# ISP-Adaptor.net
KiCad netlist of a schematic drawn in EAGLE
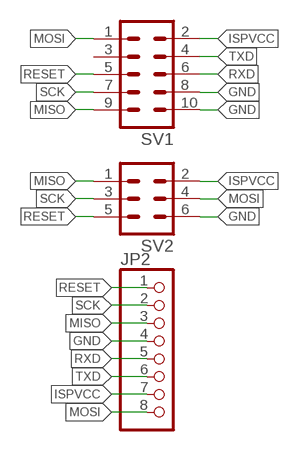
[diagram p0: schematic, sheet 1]

(export (version "E")
  (design (tool "Eeschema 10.0.6"))
  (components
    (comp (ref "JP2")
      (value "PINHD-1X8")
      (footprint "eagle-import:1X08")
      (libsource (lib "eagle-import") (part "PINHD-1X8"))
    )
    (comp (ref "SV1")
      (value "ML10")
      (footprint "eagle-import:ML10")
      (libsource (lib "eagle-import") (part "ML10"))
    )
    (comp (ref "SV2")
      (value "ML6")
      (footprint "eagle-import:ML6")
      (libsource (lib "eagle-import") (part "ML6"))
    )
  )
  (nets
    (net (code "1") (name "GND") (class "Default")
      (node (ref "JP2") (pin "4") (pinfunction "4_4") (pintype "passive"))
      (node (ref "SV1") (pin "10") (pinfunction "10_10") (pintype "passive"))
      (node (ref "SV1") (pin "8") (pinfunction "8_8") (pintype "passive"))
      (node (ref "SV2") (pin "6") (pinfunction "6_6") (pintype "passive"))
    )
    (net (code "2") (name "ISPVCC") (class "Default")
      (node (ref "JP2") (pin "7") (pinfunction "7_7") (pintype "passive"))
      (node (ref "SV1") (pin "2") (pinfunction "2_2") (pintype "passive"))
      (node (ref "SV2") (pin "2") (pinfunction "2_2") (pintype "passive"))
    )
    (net (code "3") (name "MISO") (class "Default")
      (node (ref "JP2") (pin "3") (pinfunction "3_3") (pintype "passive"))
      (node (ref "SV1") (pin "9") (pinfunction "9_9") (pintype "passive"))
      (node (ref "SV2") (pin "1") (pinfunction "1_1") (pintype "passive"))
    )
    (net (code "4") (name "MOSI") (class "Default")
      (node (ref "JP2") (pin "8") (pinfunction "8_8") (pintype "passive"))
      (node (ref "SV1") (pin "1") (pinfunction "1_1") (pintype "passive"))
      (node (ref "SV2") (pin "4") (pinfunction "4_4") (pintype "passive"))
    )
    (net (code "5") (name "RESET") (class "Default")
      (node (ref "JP2") (pin "1") (pinfunction "1_1") (pintype "passive"))
      (node (ref "SV1") (pin "5") (pinfunction "5_5") (pintype "passive"))
      (node (ref "SV2") (pin "5") (pinfunction "5_5") (pintype "passive"))
    )
    (net (code "6") (name "RXD") (class "Default")
      (node (ref "JP2") (pin "5") (pinfunction "5_5") (pintype "passive"))
      (node (ref "SV1") (pin "6") (pinfunction "6_6") (pintype "passive"))
    )
    (net (code "7") (name "SCK") (class "Default")
      (node (ref "JP2") (pin "2") (pinfunction "2_2") (pintype "passive"))
      (node (ref "SV1") (pin "7") (pinfunction "7_7") (pintype "passive"))
      (node (ref "SV2") (pin "3") (pinfunction "3_3") (pintype "passive"))
    )
    (net (code "8") (name "TXD") (class "Default")
      (node (ref "JP2") (pin "6") (pinfunction "6_6") (pintype "passive"))
      (node (ref "SV1") (pin "4") (pinfunction "4_4") (pintype "passive"))
    )
    (net (code "9") (name "unconnected-(SV1-Pad3)") (class "Default")
      (node (ref "SV1") (pin "3") (pinfunction "3_3") (pintype "passive"))
    )
  )
)
